# Alimentacion.net
KiCad netlist of a schematic drawn in Altium Designer
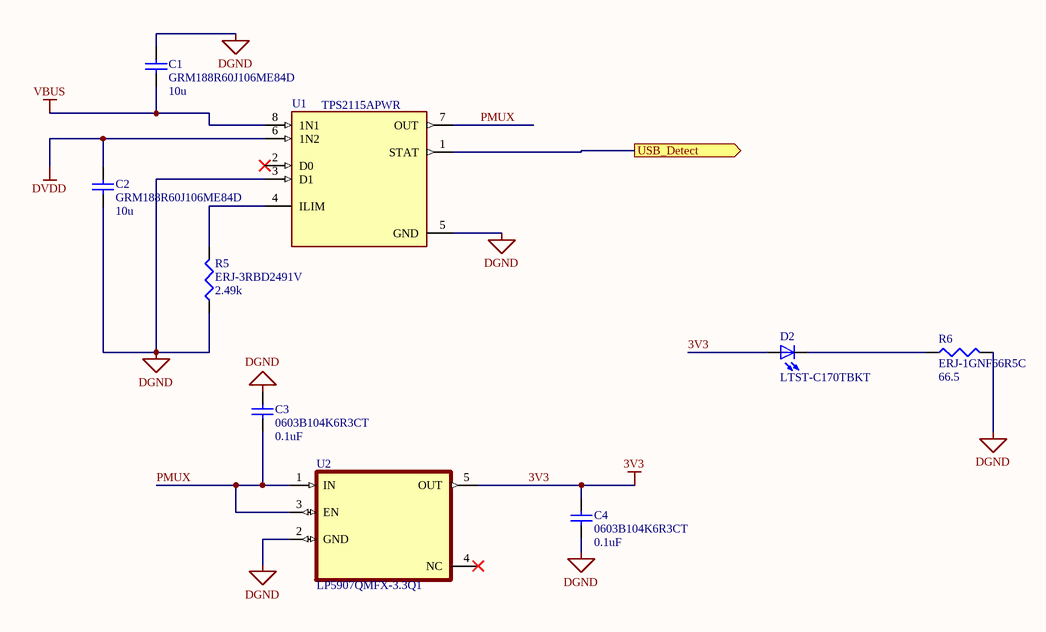
[diagram p0: Alimentacion.SchDoc]

(export (version "E")
  (design (tool "Eeschema 10.0.6"))
  (components
    (comp (ref "C1")
      (value "GRM188R60J106ME84D")
      (footprint "1608[0603]")
      (description "Capacitor (Semiconductor SIM Model)")
      (fields (field (name "ALTIUM_VALUE") "10u") (field (name "PUBLISHER") "Altium Limited"))
      (libsource (lib "Miscellaneous Devices") (part "Cap Semi"))
    )
    (comp (ref "C2")
      (value "GRM188R60J106ME84D")
      (footprint "1608[0603]")
      (description "Capacitor (Semiconductor SIM Model)")
      (fields (field (name "ALTIUM_VALUE") "10u") (field (name "PUBLISHER") "Altium Limited"))
      (libsource (lib "Miscellaneous Devices") (part "Cap Semi"))
    )
    (comp (ref "C3")
      (value "0603B104K6R3CT")
      (footprint "1608[0603]")
      (description "Capacitor (Semiconductor SIM Model)")
      (fields (field (name "ALTIUM_VALUE") "0.1uF") (field (name "PUBLISHER") "Altium Limited"))
      (libsource (lib "Miscellaneous Devices") (part "Cap Semi"))
    )
    (comp (ref "C4")
      (value "0603B104K6R3CT")
      (footprint "1608[0603]")
      (description "Capacitor (Semiconductor SIM Model)")
      (fields (field (name "ALTIUM_VALUE") "0.1uF") (field (name "PUBLISHER") "Altium Limited"))
      (libsource (lib "Miscellaneous Devices") (part "Cap Semi"))
    )
    (comp (ref "D2")
      (value "LTST-C170TBKT")
      (footprint "DIOC200X125X110")
      (description "Blue 470nm LED Indication - Discrete 3.3V 0805 _2012 Metric_")
      (fields (field (name "MF") "Lite-On Inc.") (field (name "DIGI-KEY_PART_NUMBER") "160-1579-1-ND"))
      (libsource (lib "Led") (part "LTST-C170TBKT"))
    )
    (comp (ref "R5")
      (value "ERJ-3RBD2491V")
      (footprint "J1-0603")
      (description "Resistor")
      (fields (field (name "ALTIUM_VALUE") "2.49k") (field (name "PUBLISHER") "Altium Limited"))
      (libsource (lib "Miscellaneous Devices") (part "Res3"))
    )
    (comp (ref "R6")
      (value "ERJ-1GNF66R5C")
      (footprint "J1-0603")
      (description "Resistor")
      (fields (field (name "ALTIUM_VALUE") "66.5") (field (name "PUBLISHER") "Altium Limited"))
      (libsource (lib "Miscellaneous Devices") (part "Res3"))
    )
    (comp (ref "U1")
      (value "TPS2115APWR")
      (footprint "SOP65P640X120-8N")
      (libsource (lib "TPS2115APWR") (part "TPS2115APWR"))
    )
    (comp (ref "U2")
      (value "LP5907QMFX-3.3Q1")
      (footprint "SOT95P280X145-5N")
      (fields (field (name "MF") "Texas Instruments"))
      (libsource (lib "LP5907QMFX-3.3Q1") (part "LP5907QMFX-3.3Q1"))
    )
  )
  (nets
    (net (code "1") (name "/PMUX") (class "Default")
      (node (ref "C3") (pin "1") (pinfunction "1_1") (pintype "passive"))
      (node (ref "U1") (pin "7") (pinfunction "OUT_7") (pintype "output"))
      (node (ref "U2") (pin "1") (pinfunction "IN_1") (pintype "input"))
      (node (ref "U2") (pin "3") (pinfunction "EN_3") (pintype "bidirectional"))
    )
    (net (code "2") (name "/USB_Detect") (class "Default")
      (node (ref "U1") (pin "1") (pinfunction "STAT_1") (pintype "output"))
    )
    (net (code "3") (name "3V3") (class "Default")
      (node (ref "C4") (pin "2") (pinfunction "2_2") (pintype "passive"))
      (node (ref "D2") (pin "POS") (pinfunction "POS_POS") (pintype "passive"))
      (node (ref "U2") (pin "5") (pinfunction "OUT_5") (pintype "output"))
    )
    (net (code "4") (name "DGND") (class "Default")
      (node (ref "C1") (pin "2") (pinfunction "2_2") (pintype "passive"))
      (node (ref "C2") (pin "1") (pinfunction "1_1") (pintype "passive"))
      (node (ref "C3") (pin "2") (pinfunction "2_2") (pintype "passive"))
      (node (ref "C4") (pin "1") (pinfunction "1_1") (pintype "passive"))
      (node (ref "R5") (pin "1") (pinfunction "1_1") (pintype "passive"))
      (node (ref "R6") (pin "2") (pinfunction "2_2") (pintype "passive"))
      (node (ref "U1") (pin "3") (pinfunction "D1_3") (pintype "input"))
      (node (ref "U1") (pin "5") (pinfunction "GND_5") (pintype "power_in"))
      (node (ref "U2") (pin "2") (pinfunction "GND_2") (pintype "bidirectional"))
    )
    (net (code "5") (name "DVDD") (class "Default")
      (node (ref "C2") (pin "2") (pinfunction "2_2") (pintype "passive"))
      (node (ref "U1") (pin "6") (pinfunction "1N2_6") (pintype "input"))
    )
    (net (code "6") (name "Net-(D2-PadNEG)") (class "Default")
      (node (ref "D2") (pin "NEG") (pinfunction "NEG_NEG") (pintype "passive"))
      (node (ref "R6") (pin "1") (pinfunction "1_1") (pintype "passive"))
    )
    (net (code "7") (name "Net-(U1-ILIM)") (class "Default")
      (node (ref "R5") (pin "2") (pinfunction "2_2") (pintype "passive"))
      (node (ref "U1") (pin "4") (pinfunction "ILIM_4") (pintype "passive"))
    )
    (net (code "8") (name "VBUS") (class "Default")
      (node (ref "C1") (pin "1") (pinfunction "1_1") (pintype "passive"))
      (node (ref "U1") (pin "8") (pinfunction "1N1_8") (pintype "input"))
    )
    (net (code "9") (name "unconnected-(U1-D0-Pad2)") (class "Default")
      (node (ref "U1") (pin "2") (pinfunction "D0_2") (pintype "input+no_connect"))
    )
    (net (code "10") (name "unconnected-(U2-NC-Pad4)") (class "Default")
      (node (ref "U2") (pin "4") (pinfunction "NC_4") (pintype "power_in+no_connect"))
    )
  )
)
